# Easy_EDA_-_Maltron_S_Edition_-_Schematic.net
KiCad netlist of a schematic drawn in EasyEDA
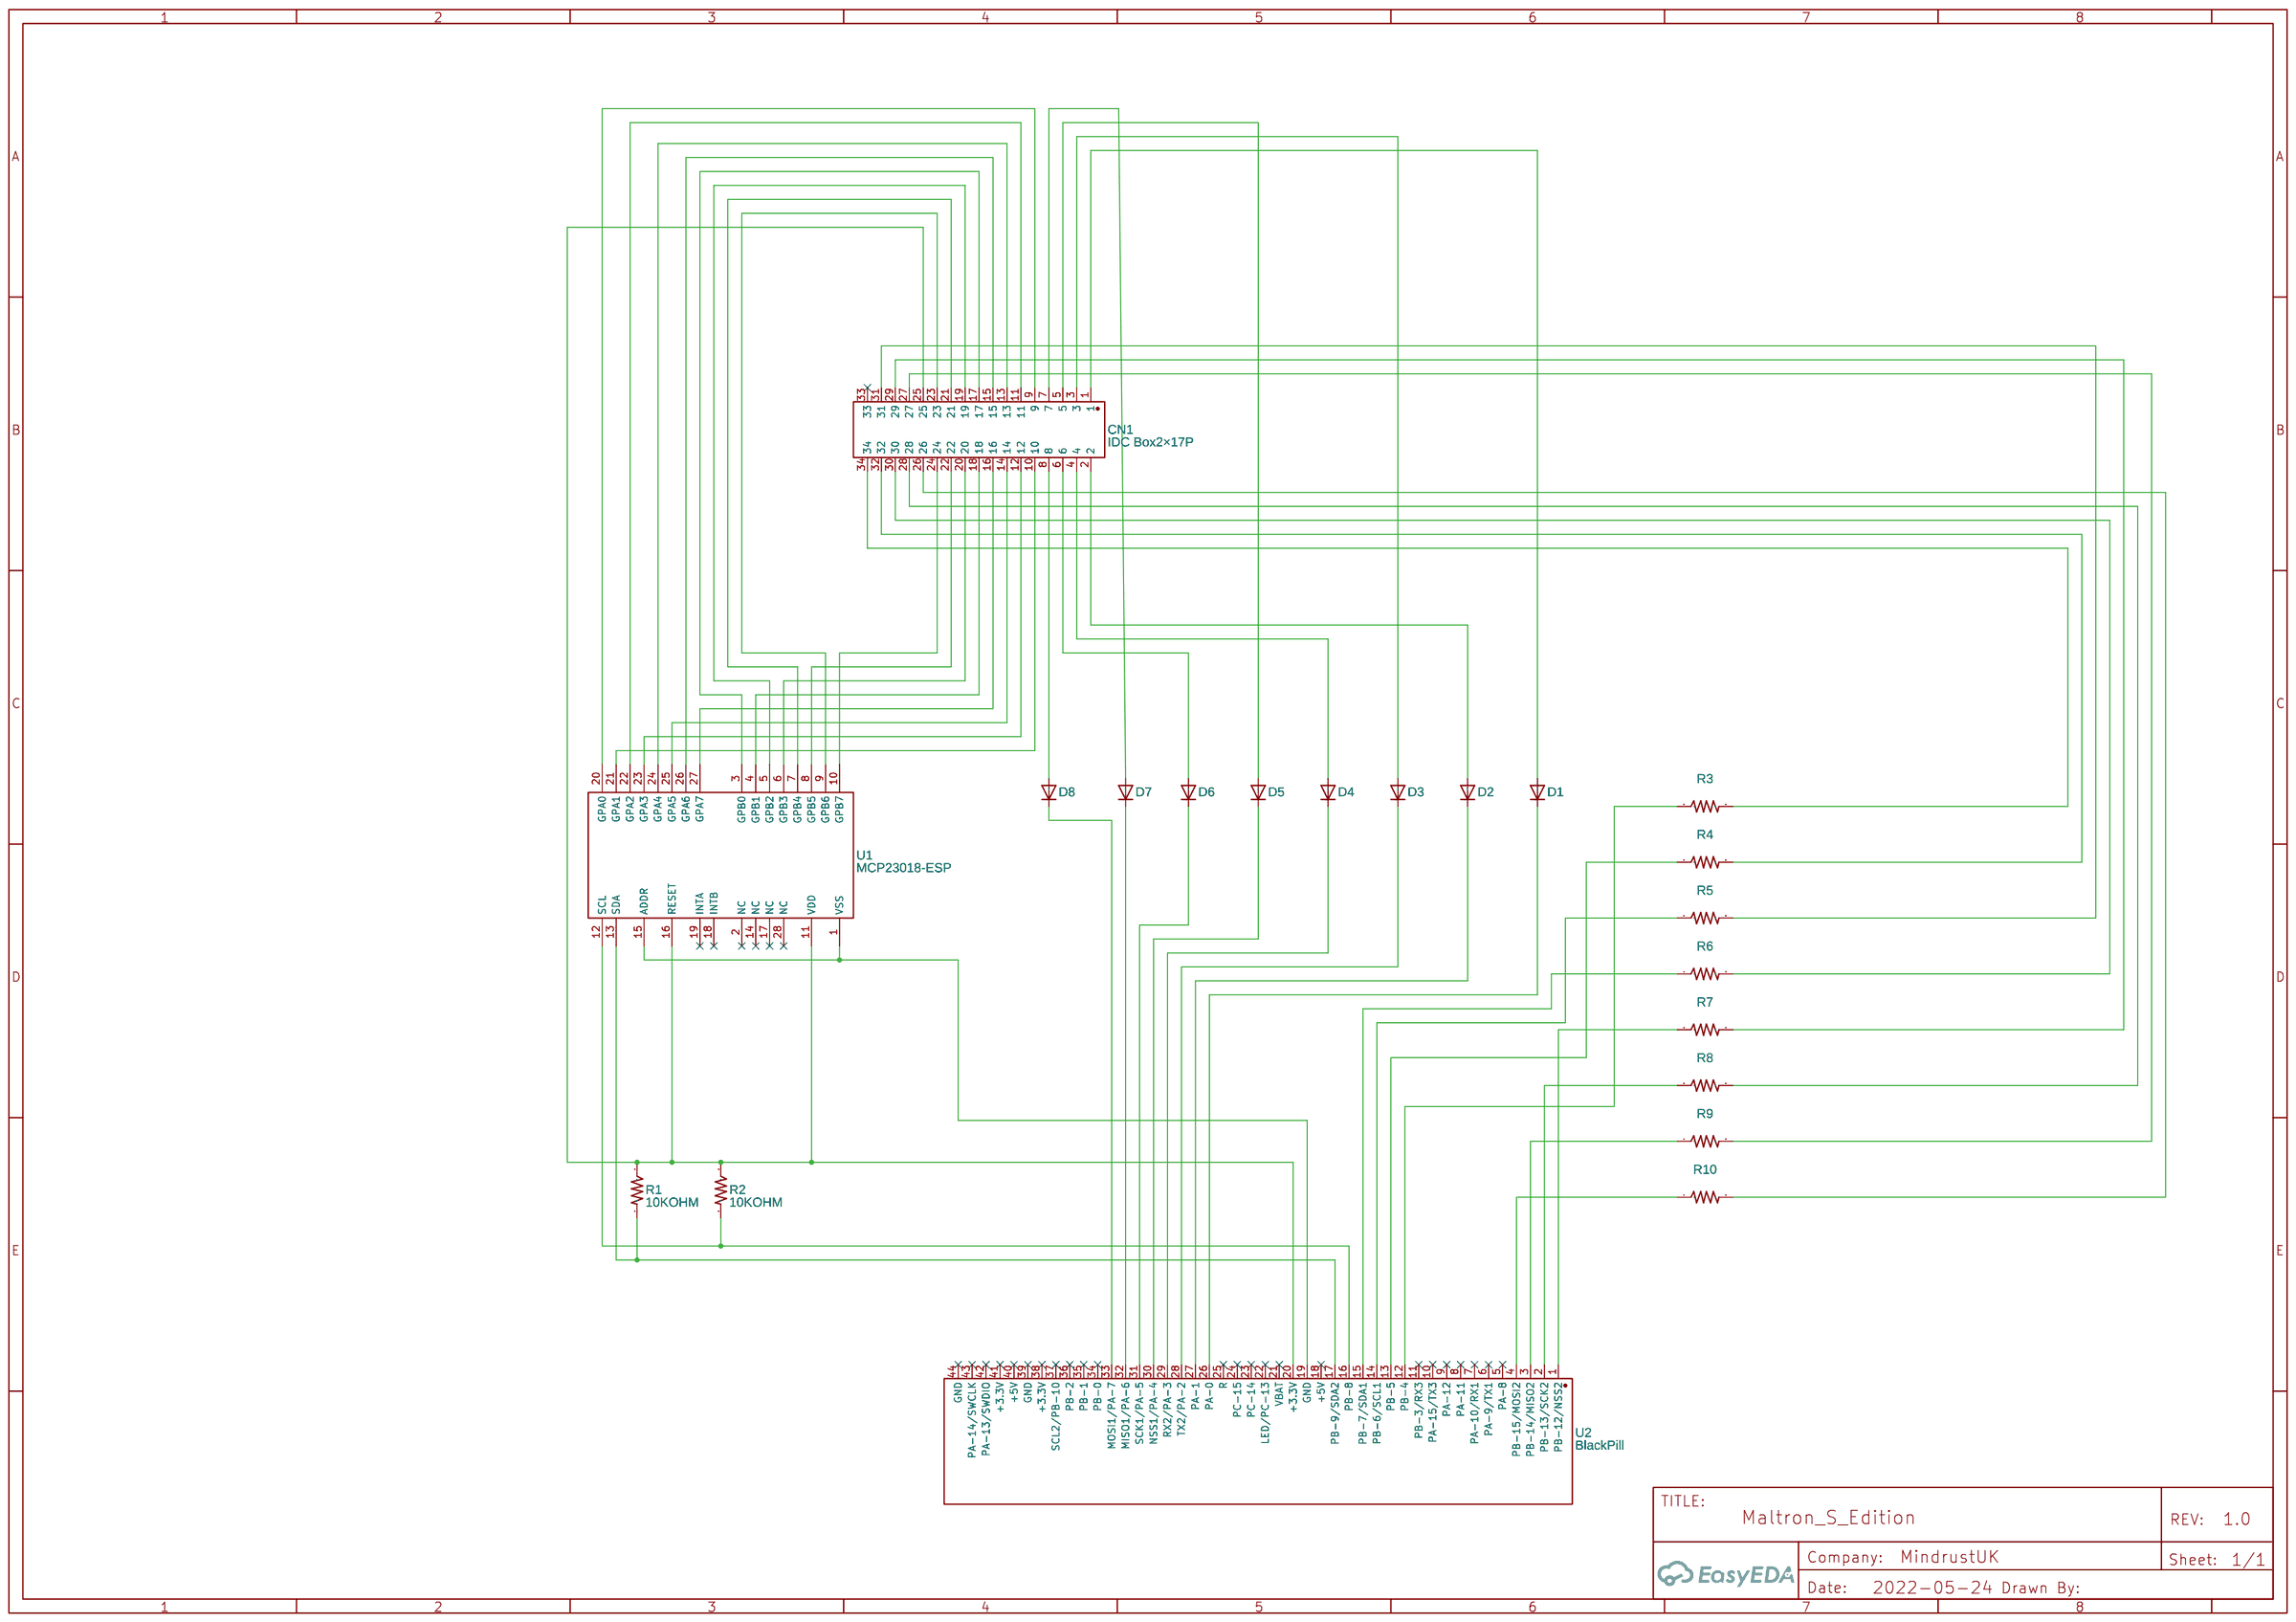
[diagram p0: schematic sheet]

(export (version "E")
  (design (tool "Eeschema 10.0.6"))
  (components
    (comp (ref "CN1")
      (value "IDC Box2×17P")
      (fields
        (field (name "BOM_Manufacturer Part") "IDC Box2×17P Right Angle")
        (field (name "BOM_Supplier Part") "C20920")
      )
      (libsource (lib "") (part "IDC Box2×17P"))
    )
    (comp (ref "D1") (value "DIODE") (libsource (lib "") (part "DIODE")))
    (comp (ref "D2") (value "DIODE") (libsource (lib "") (part "DIODE")))
    (comp (ref "D3") (value "DIODE") (libsource (lib "") (part "DIODE")))
    (comp (ref "D4") (value "DIODE") (libsource (lib "") (part "DIODE")))
    (comp (ref "D5") (value "DIODE") (libsource (lib "") (part "DIODE")))
    (comp (ref "D6") (value "DIODE") (libsource (lib "") (part "DIODE")))
    (comp (ref "D7") (value "DIODE") (libsource (lib "") (part "DIODE")))
    (comp (ref "D8") (value "DIODE") (libsource (lib "") (part "DIODE")))
    (comp (ref "R1") (value "10KOHM") (libsource (lib "") (part "10KOHM-1_4W5%(PTH)HORIZ-KIT")))
    (comp (ref "R2") (value "10KOHM") (libsource (lib "") (part "10KOHM-1_4W5%(PTH)HORIZ-KIT")))
    (comp (ref "R3")
      (value "10OHM-1_4W-5%(PTH)HORIZ-KIT")
      (libsource (lib "") (part "10OHM-1_4W-5%(PTH)HORIZ-KIT"))
    )
    (comp (ref "R4")
      (value "10OHM-1_4W-5%(PTH)HORIZ-KIT")
      (libsource (lib "") (part "10OHM-1_4W-5%(PTH)HORIZ-KIT"))
    )
    (comp (ref "R5")
      (value "10OHM-1_4W-5%(PTH)HORIZ-KIT")
      (libsource (lib "") (part "10OHM-1_4W-5%(PTH)HORIZ-KIT"))
    )
    (comp (ref "R6")
      (value "10OHM-1_4W-5%(PTH)HORIZ-KIT")
      (libsource (lib "") (part "10OHM-1_4W-5%(PTH)HORIZ-KIT"))
    )
    (comp (ref "R7")
      (value "10OHM-1_4W-5%(PTH)HORIZ-KIT")
      (libsource (lib "") (part "10OHM-1_4W-5%(PTH)HORIZ-KIT"))
    )
    (comp (ref "R8")
      (value "10OHM-1_4W-5%(PTH)HORIZ-KIT")
      (libsource (lib "") (part "10OHM-1_4W-5%(PTH)HORIZ-KIT"))
    )
    (comp (ref "R9")
      (value "10OHM-1_4W-5%(PTH)HORIZ-KIT")
      (libsource (lib "") (part "10OHM-1_4W-5%(PTH)HORIZ-KIT"))
    )
    (comp (ref "R10")
      (value "10OHM-1_4W-5%(PTH)HORIZ-KIT")
      (libsource (lib "") (part "10OHM-1_4W-5%(PTH)HORIZ-KIT"))
    )
    (comp (ref "U1") (value "MCP23018-ESP") (libsource (lib "") (part "MCP23018-ESP")))
    (comp (ref "U2") (value "BlackPill") (libsource (lib "") (part "BlackPill")))
  )
  (nets
    (net (code "1") (name "Net-(CN1-Pad1)") (class "Default")
      (node (ref "CN1") (pin "1") (pinfunction "1_1") (pintype "unspecified"))
      (node (ref "D1") (pin "A") (pinfunction "A_A") (pintype "unspecified"))
    )
    (net (code "2") (name "Net-(CN1-Pad2)") (class "Default")
      (node (ref "CN1") (pin "2") (pinfunction "2_2") (pintype "unspecified"))
      (node (ref "D2") (pin "A") (pinfunction "A_A") (pintype "unspecified"))
    )
    (net (code "3") (name "Net-(CN1-Pad3)") (class "Default")
      (node (ref "CN1") (pin "3") (pinfunction "3_3") (pintype "unspecified"))
      (node (ref "D3") (pin "A") (pinfunction "A_A") (pintype "unspecified"))
    )
    (net (code "4") (name "Net-(CN1-Pad4)") (class "Default")
      (node (ref "CN1") (pin "4") (pinfunction "4_4") (pintype "unspecified"))
      (node (ref "D4") (pin "A") (pinfunction "A_A") (pintype "unspecified"))
    )
    (net (code "5") (name "Net-(CN1-Pad5)") (class "Default")
      (node (ref "CN1") (pin "5") (pinfunction "5_5") (pintype "unspecified"))
      (node (ref "D5") (pin "A") (pinfunction "A_A") (pintype "unspecified"))
    )
    (net (code "6") (name "Net-(CN1-Pad6)") (class "Default")
      (node (ref "CN1") (pin "6") (pinfunction "6_6") (pintype "unspecified"))
      (node (ref "D6") (pin "A") (pinfunction "A_A") (pintype "unspecified"))
    )
    (net (code "7") (name "Net-(CN1-Pad7)") (class "Default")
      (node (ref "CN1") (pin "7") (pinfunction "7_7") (pintype "unspecified"))
      (node (ref "D7") (pin "A") (pinfunction "A_A") (pintype "unspecified"))
    )
    (net (code "8") (name "Net-(CN1-Pad8)") (class "Default")
      (node (ref "CN1") (pin "8") (pinfunction "8_8") (pintype "unspecified"))
      (node (ref "D8") (pin "A") (pinfunction "A_A") (pintype "unspecified"))
    )
    (net (code "9") (name "Net-(CN1-Pad26)") (class "Default")
      (node (ref "CN1") (pin "26") (pinfunction "26_26") (pintype "unspecified"))
      (node (ref "R10") (pin "2") (pinfunction "2_2") (pintype "unspecified"))
    )
    (net (code "10") (name "Net-(CN1-Pad27)") (class "Default")
      (node (ref "CN1") (pin "27") (pinfunction "27_27") (pintype "unspecified"))
      (node (ref "R9") (pin "2") (pinfunction "2_2") (pintype "unspecified"))
    )
    (net (code "11") (name "Net-(CN1-Pad28)") (class "Default")
      (node (ref "CN1") (pin "28") (pinfunction "28_28") (pintype "unspecified"))
      (node (ref "R8") (pin "2") (pinfunction "2_2") (pintype "unspecified"))
    )
    (net (code "12") (name "Net-(CN1-Pad29)") (class "Default")
      (node (ref "CN1") (pin "29") (pinfunction "29_29") (pintype "unspecified"))
      (node (ref "R7") (pin "2") (pinfunction "2_2") (pintype "unspecified"))
    )
    (net (code "13") (name "Net-(CN1-Pad30)") (class "Default")
      (node (ref "CN1") (pin "30") (pinfunction "30_30") (pintype "unspecified"))
      (node (ref "R6") (pin "2") (pinfunction "2_2") (pintype "unspecified"))
    )
    (net (code "14") (name "Net-(CN1-Pad31)") (class "Default")
      (node (ref "CN1") (pin "31") (pinfunction "31_31") (pintype "unspecified"))
      (node (ref "R5") (pin "2") (pinfunction "2_2") (pintype "unspecified"))
    )
    (net (code "15") (name "Net-(CN1-Pad32)") (class "Default")
      (node (ref "CN1") (pin "32") (pinfunction "32_32") (pintype "unspecified"))
      (node (ref "R4") (pin "2") (pinfunction "2_2") (pintype "unspecified"))
    )
    (net (code "16") (name "Net-(CN1-Pad34)") (class "Default")
      (node (ref "CN1") (pin "34") (pinfunction "34_34") (pintype "unspecified"))
      (node (ref "R3") (pin "2") (pinfunction "2_2") (pintype "unspecified"))
    )
    (net (code "17") (name "Net-(U1-ADDR)") (class "Default")
      (node (ref "U1") (pin "1") (pinfunction "VSS_1") (pintype "passive"))
      (node (ref "U1") (pin "15") (pinfunction "ADDR_15") (pintype "unspecified"))
      (node (ref "U2") (pin "19") (pinfunction "GND_19") (pintype "unspecified"))
    )
    (net (code "18") (name "Net-(U1-GPA0)") (class "Default")
      (node (ref "CN1") (pin "9") (pinfunction "9_9") (pintype "unspecified"))
      (node (ref "U1") (pin "20") (pinfunction "GPA0_20") (pintype "bidirectional"))
    )
    (net (code "19") (name "Net-(U1-GPA1)") (class "Default")
      (node (ref "CN1") (pin "10") (pinfunction "10_10") (pintype "unspecified"))
      (node (ref "U1") (pin "21") (pinfunction "GPA1_21") (pintype "bidirectional"))
    )
    (net (code "20") (name "Net-(U1-GPA2)") (class "Default")
      (node (ref "CN1") (pin "11") (pinfunction "11_11") (pintype "unspecified"))
      (node (ref "U1") (pin "22") (pinfunction "GPA2_22") (pintype "bidirectional"))
    )
    (net (code "21") (name "Net-(U1-GPA3)") (class "Default")
      (node (ref "CN1") (pin "12") (pinfunction "12_12") (pintype "unspecified"))
      (node (ref "U1") (pin "23") (pinfunction "GPA3_23") (pintype "bidirectional"))
    )
    (net (code "22") (name "Net-(U1-GPA4)") (class "Default")
      (node (ref "CN1") (pin "13") (pinfunction "13_13") (pintype "unspecified"))
      (node (ref "U1") (pin "24") (pinfunction "GPA4_24") (pintype "bidirectional"))
    )
    (net (code "23") (name "Net-(U1-GPA5)") (class "Default")
      (node (ref "CN1") (pin "14") (pinfunction "14_14") (pintype "unspecified"))
      (node (ref "U1") (pin "25") (pinfunction "GPA5_25") (pintype "bidirectional"))
    )
    (net (code "24") (name "Net-(U1-GPA6)") (class "Default")
      (node (ref "CN1") (pin "15") (pinfunction "15_15") (pintype "unspecified"))
      (node (ref "U1") (pin "26") (pinfunction "GPA6_26") (pintype "bidirectional"))
    )
    (net (code "25") (name "Net-(U1-GPA7)") (class "Default")
      (node (ref "CN1") (pin "16") (pinfunction "16_16") (pintype "unspecified"))
      (node (ref "U1") (pin "27") (pinfunction "GPA7_27") (pintype "bidirectional"))
    )
    (net (code "26") (name "Net-(U1-GPB0)") (class "Default")
      (node (ref "CN1") (pin "17") (pinfunction "17_17") (pintype "unspecified"))
      (node (ref "U1") (pin "3") (pinfunction "GPB0_3") (pintype "bidirectional"))
    )
    (net (code "27") (name "Net-(U1-GPB1)") (class "Default")
      (node (ref "CN1") (pin "18") (pinfunction "18_18") (pintype "unspecified"))
      (node (ref "U1") (pin "4") (pinfunction "GPB1_4") (pintype "bidirectional"))
    )
    (net (code "28") (name "Net-(U1-GPB2)") (class "Default")
      (node (ref "CN1") (pin "19") (pinfunction "19_19") (pintype "unspecified"))
      (node (ref "U1") (pin "5") (pinfunction "GPB2_5") (pintype "bidirectional"))
    )
    (net (code "29") (name "Net-(U1-GPB3)") (class "Default")
      (node (ref "CN1") (pin "20") (pinfunction "20_20") (pintype "unspecified"))
      (node (ref "U1") (pin "6") (pinfunction "GPB3_6") (pintype "bidirectional"))
    )
    (net (code "30") (name "Net-(U1-GPB4)") (class "Default")
      (node (ref "CN1") (pin "21") (pinfunction "21_21") (pintype "unspecified"))
      (node (ref "U1") (pin "7") (pinfunction "GPB4_7") (pintype "bidirectional"))
    )
    (net (code "31") (name "Net-(U1-GPB5)") (class "Default")
      (node (ref "CN1") (pin "22") (pinfunction "22_22") (pintype "unspecified"))
      (node (ref "U1") (pin "8") (pinfunction "GPB5_8") (pintype "bidirectional"))
    )
    (net (code "32") (name "Net-(U1-GPB6)") (class "Default")
      (node (ref "CN1") (pin "23") (pinfunction "23_23") (pintype "unspecified"))
      (node (ref "U1") (pin "9") (pinfunction "GPB6_9") (pintype "bidirectional"))
    )
    (net (code "33") (name "Net-(U1-GPB7)") (class "Default")
      (node (ref "CN1") (pin "24") (pinfunction "24_24") (pintype "unspecified"))
      (node (ref "U1") (pin "10") (pinfunction "GPB7_10") (pintype "bidirectional"))
    )
    (net (code "34") (name "Net-(U1-RESET)") (class "Default")
      (node (ref "CN1") (pin "25") (pinfunction "25_25") (pintype "unspecified"))
      (node (ref "R1") (pin "1") (pinfunction "1_1") (pintype "unspecified"))
      (node (ref "R2") (pin "1") (pinfunction "1_1") (pintype "unspecified"))
      (node (ref "U1") (pin "11") (pinfunction "VDD_11") (pintype "passive"))
      (node (ref "U1") (pin "16") (pinfunction "RESET_16") (pintype "unspecified"))
      (node (ref "U2") (pin "20") (pinfunction "+3.3V_20") (pintype "unspecified"))
    )
    (net (code "35") (name "Net-(U1-SCL)") (class "Default")
      (node (ref "R2") (pin "2") (pinfunction "2_2") (pintype "unspecified"))
      (node (ref "U1") (pin "12") (pinfunction "SCL_12") (pintype "unspecified"))
      (node (ref "U2") (pin "16") (pinfunction "PB-8_16") (pintype "unspecified"))
    )
    (net (code "36") (name "Net-(U1-SDA)") (class "Default")
      (node (ref "R1") (pin "2") (pinfunction "2_2") (pintype "unspecified"))
      (node (ref "U1") (pin "13") (pinfunction "SDA_13") (pintype "bidirectional"))
      (node (ref "U2") (pin "17") (pinfunction "PB-9/SDA2_17") (pintype "unspecified"))
    )
    (net (code "37") (name "Net-(U2-MISO1{slash}PA-6)") (class "Default")
      (node (ref "D7") (pin "C") (pinfunction "C_C") (pintype "unspecified"))
      (node (ref "U2") (pin "32") (pinfunction "MISO1/PA-6_32") (pintype "unspecified"))
    )
    (net (code "38") (name "Net-(U2-MOSI1{slash}PA-7)") (class "Default")
      (node (ref "D8") (pin "C") (pinfunction "C_C") (pintype "unspecified"))
      (node (ref "U2") (pin "33") (pinfunction "MOSI1/PA-7_33") (pintype "unspecified"))
    )
    (net (code "39") (name "Net-(U2-NSS1{slash}PA-4)") (class "Default")
      (node (ref "D5") (pin "C") (pinfunction "C_C") (pintype "unspecified"))
      (node (ref "U2") (pin "30") (pinfunction "NSS1/PA-4_30") (pintype "unspecified"))
    )
    (net (code "40") (name "Net-(U2-PA-0)") (class "Default")
      (node (ref "D1") (pin "C") (pinfunction "C_C") (pintype "unspecified"))
      (node (ref "U2") (pin "26") (pinfunction "PA-0_26") (pintype "unspecified"))
    )
    (net (code "41") (name "Net-(U2-PA-1)") (class "Default")
      (node (ref "D2") (pin "C") (pinfunction "C_C") (pintype "unspecified"))
      (node (ref "U2") (pin "27") (pinfunction "PA-1_27") (pintype "unspecified"))
    )
    (net (code "42") (name "Net-(U2-PB-4)") (class "Default")
      (node (ref "R3") (pin "1") (pinfunction "1_1") (pintype "unspecified"))
      (node (ref "U2") (pin "12") (pinfunction "PB-4_12") (pintype "unspecified"))
    )
    (net (code "43") (name "Net-(U2-PB-5)") (class "Default")
      (node (ref "R4") (pin "1") (pinfunction "1_1") (pintype "unspecified"))
      (node (ref "U2") (pin "13") (pinfunction "PB-5_13") (pintype "unspecified"))
    )
    (net (code "44") (name "Net-(U2-PB-6{slash}SCL1)") (class "Default")
      (node (ref "R5") (pin "1") (pinfunction "1_1") (pintype "unspecified"))
      (node (ref "U2") (pin "14") (pinfunction "PB-6/SCL1_14") (pintype "unspecified"))
    )
    (net (code "45") (name "Net-(U2-PB-7{slash}SDA1)") (class "Default")
      (node (ref "R6") (pin "1") (pinfunction "1_1") (pintype "unspecified"))
      (node (ref "U2") (pin "15") (pinfunction "PB-7/SDA1_15") (pintype "unspecified"))
    )
    (net (code "46") (name "Net-(U2-PB-12{slash}NSS2)") (class "Default")
      (node (ref "R7") (pin "1") (pinfunction "1_1") (pintype "unspecified"))
      (node (ref "U2") (pin "1") (pinfunction "PB-12/NSS2_1") (pintype "unspecified"))
    )
    (net (code "47") (name "Net-(U2-PB-13{slash}SCK2)") (class "Default")
      (node (ref "R8") (pin "1") (pinfunction "1_1") (pintype "unspecified"))
      (node (ref "U2") (pin "2") (pinfunction "PB-13/SCK2_2") (pintype "unspecified"))
    )
    (net (code "48") (name "Net-(U2-PB-14{slash}MISO2)") (class "Default")
      (node (ref "R9") (pin "1") (pinfunction "1_1") (pintype "unspecified"))
      (node (ref "U2") (pin "3") (pinfunction "PB-14/MISO2_3") (pintype "unspecified"))
    )
    (net (code "49") (name "Net-(U2-PB-15{slash}MOSI2)") (class "Default")
      (node (ref "R10") (pin "1") (pinfunction "1_1") (pintype "unspecified"))
      (node (ref "U2") (pin "4") (pinfunction "PB-15/MOSI2_4") (pintype "unspecified"))
    )
    (net (code "50") (name "Net-(U2-RX2{slash}PA-3)") (class "Default")
      (node (ref "D4") (pin "C") (pinfunction "C_C") (pintype "unspecified"))
      (node (ref "U2") (pin "29") (pinfunction "RX2/PA-3_29") (pintype "unspecified"))
    )
    (net (code "51") (name "Net-(U2-SCK1{slash}PA-5)") (class "Default")
      (node (ref "D6") (pin "C") (pinfunction "C_C") (pintype "unspecified"))
      (node (ref "U2") (pin "31") (pinfunction "SCK1/PA-5_31") (pintype "unspecified"))
    )
    (net (code "52") (name "Net-(U2-TX2{slash}PA-2)") (class "Default")
      (node (ref "D3") (pin "C") (pinfunction "C_C") (pintype "unspecified"))
      (node (ref "U2") (pin "28") (pinfunction "TX2/PA-2_28") (pintype "unspecified"))
    )
    (net (code "53") (name "unconnected-(CN1-Pad33)") (class "Default")
      (node (ref "CN1") (pin "33") (pinfunction "33_33") (pintype "unspecified+no_connect"))
    )
    (net (code "54") (name "unconnected-(U1-INTA-Pad19)") (class "Default")
      (node (ref "U1") (pin "19") (pinfunction "INTA_19") (pintype "unspecified+no_connect"))
    )
    (net (code "55") (name "unconnected-(U1-INTB-Pad18)") (class "Default")
      (node (ref "U1") (pin "18") (pinfunction "INTB_18") (pintype "unspecified+no_connect"))
    )
    (net (code "56") (name "unconnected-(U1-NC-Pad2)") (class "Default")
      (node (ref "U1") (pin "2") (pinfunction "NC_2") (pintype "unspecified+no_connect"))
    )
    (net (code "57") (name "unconnected-(U1-NC-Pad14)") (class "Default")
      (node (ref "U1") (pin "14") (pinfunction "NC_14") (pintype "unspecified+no_connect"))
    )
    (net (code "58") (name "unconnected-(U1-NC-Pad17)") (class "Default")
      (node (ref "U1") (pin "17") (pinfunction "NC_17") (pintype "unspecified+no_connect"))
    )
    (net (code "59") (name "unconnected-(U1-NC-Pad28)") (class "Default")
      (node (ref "U1") (pin "28") (pinfunction "NC_28") (pintype "unspecified+no_connect"))
    )
    (net (code "60") (name "unconnected-(U2-+3.3V-Pad38)") (class "Default")
      (node (ref "U2") (pin "38") (pinfunction "+3.3V_38") (pintype "unspecified+no_connect"))
    )
    (net (code "61") (name "unconnected-(U2-+3.3V-Pad41)") (class "Default")
      (node (ref "U2") (pin "41") (pinfunction "+3.3V_41") (pintype "unspecified+no_connect"))
    )
    (net (code "62") (name "unconnected-(U2-+5V-Pad18)") (class "Default")
      (node (ref "U2") (pin "18") (pinfunction "+5V_18") (pintype "unspecified+no_connect"))
    )
    (net (code "63") (name "unconnected-(U2-+5V-Pad40)") (class "Default")
      (node (ref "U2") (pin "40") (pinfunction "+5V_40") (pintype "unspecified+no_connect"))
    )
    (net (code "64") (name "unconnected-(U2-GND-Pad39)") (class "Default")
      (node (ref "U2") (pin "39") (pinfunction "GND_39") (pintype "unspecified+no_connect"))
    )
    (net (code "65") (name "unconnected-(U2-GND-Pad44)") (class "Default")
      (node (ref "U2") (pin "44") (pinfunction "GND_44") (pintype "unspecified+no_connect"))
    )
    (net (code "66") (name "unconnected-(U2-LED{slash}PC-13-Pad22)") (class "Default")
      (node (ref "U2") (pin "22") (pinfunction "LED/PC-13_22") (pintype "unspecified+no_connect"))
    )
    (net (code "67") (name "unconnected-(U2-PA-8-Pad5)") (class "Default")
      (node (ref "U2") (pin "5") (pinfunction "PA-8_5") (pintype "unspecified+no_connect"))
    )
    (net (code "68") (name "unconnected-(U2-PA-9{slash}TX1-Pad6)") (class "Default")
      (node (ref "U2") (pin "6") (pinfunction "PA-9/TX1_6") (pintype "unspecified+no_connect"))
    )
    (net (code "69") (name "unconnected-(U2-PA-10{slash}RX1-Pad7)") (class "Default")
      (node (ref "U2") (pin "7") (pinfunction "PA-10/RX1_7") (pintype "unspecified+no_connect"))
    )
    (net (code "70") (name "unconnected-(U2-PA-11-Pad8)") (class "Default")
      (node (ref "U2") (pin "8") (pinfunction "PA-11_8") (pintype "unspecified+no_connect"))
    )
    (net (code "71") (name "unconnected-(U2-PA-12-Pad9)") (class "Default")
      (node (ref "U2") (pin "9") (pinfunction "PA-12_9") (pintype "unspecified+no_connect"))
    )
    (net (code "72") (name "unconnected-(U2-PA-13{slash}SWDIO-Pad42)") (class "Default")
      (node (ref "U2") (pin "42") (pinfunction "PA-13/SWDIO_42") (pintype "unspecified+no_connect"))
    )
    (net (code "73") (name "unconnected-(U2-PA-14{slash}SWCLK-Pad43)") (class "Default")
      (node (ref "U2") (pin "43") (pinfunction "PA-14/SWCLK_43") (pintype "unspecified+no_connect"))
    )
    (net (code "74") (name "unconnected-(U2-PA-15{slash}TX3-Pad10)") (class "Default")
      (node (ref "U2") (pin "10") (pinfunction "PA-15/TX3_10") (pintype "unspecified+no_connect"))
    )
    (net (code "75") (name "unconnected-(U2-PB-0-Pad34)") (class "Default")
      (node (ref "U2") (pin "34") (pinfunction "PB-0_34") (pintype "unspecified+no_connect"))
    )
    (net (code "76") (name "unconnected-(U2-PB-1-Pad35)") (class "Default")
      (node (ref "U2") (pin "35") (pinfunction "PB-1_35") (pintype "unspecified+no_connect"))
    )
    (net (code "77") (name "unconnected-(U2-PB-2-Pad36)") (class "Default")
      (node (ref "U2") (pin "36") (pinfunction "PB-2_36") (pintype "unspecified+no_connect"))
    )
    (net (code "78") (name "unconnected-(U2-PB-3{slash}RX3-Pad11)") (class "Default")
      (node (ref "U2") (pin "11") (pinfunction "PB-3/RX3_11") (pintype "unspecified+no_connect"))
    )
    (net (code "79") (name "unconnected-(U2-PC-14-Pad23)") (class "Default")
      (node (ref "U2") (pin "23") (pinfunction "PC-14_23") (pintype "unspecified+no_connect"))
    )
    (net (code "80") (name "unconnected-(U2-PC-15-Pad24)") (class "Default")
      (node (ref "U2") (pin "24") (pinfunction "PC-15_24") (pintype "unspecified+no_connect"))
    )
    (net (code "81") (name "unconnected-(U2-R-Pad25)") (class "Default")
      (node (ref "U2") (pin "25") (pinfunction "R_25") (pintype "unspecified+no_connect"))
    )
    (net (code "82") (name "unconnected-(U2-SCL2{slash}PB-10-Pad37)") (class "Default")
      (node (ref "U2") (pin "37") (pinfunction "SCL2/PB-10_37") (pintype "unspecified+no_connect"))
    )
    (net (code "83") (name "unconnected-(U2-VBAT-Pad21)") (class "Default")
      (node (ref "U2") (pin "21") (pinfunction "VBAT_21") (pintype "unspecified+no_connect"))
    )
  )
)
